# Power_Regulation.net
KiCad netlist of a schematic drawn in Altium Designer
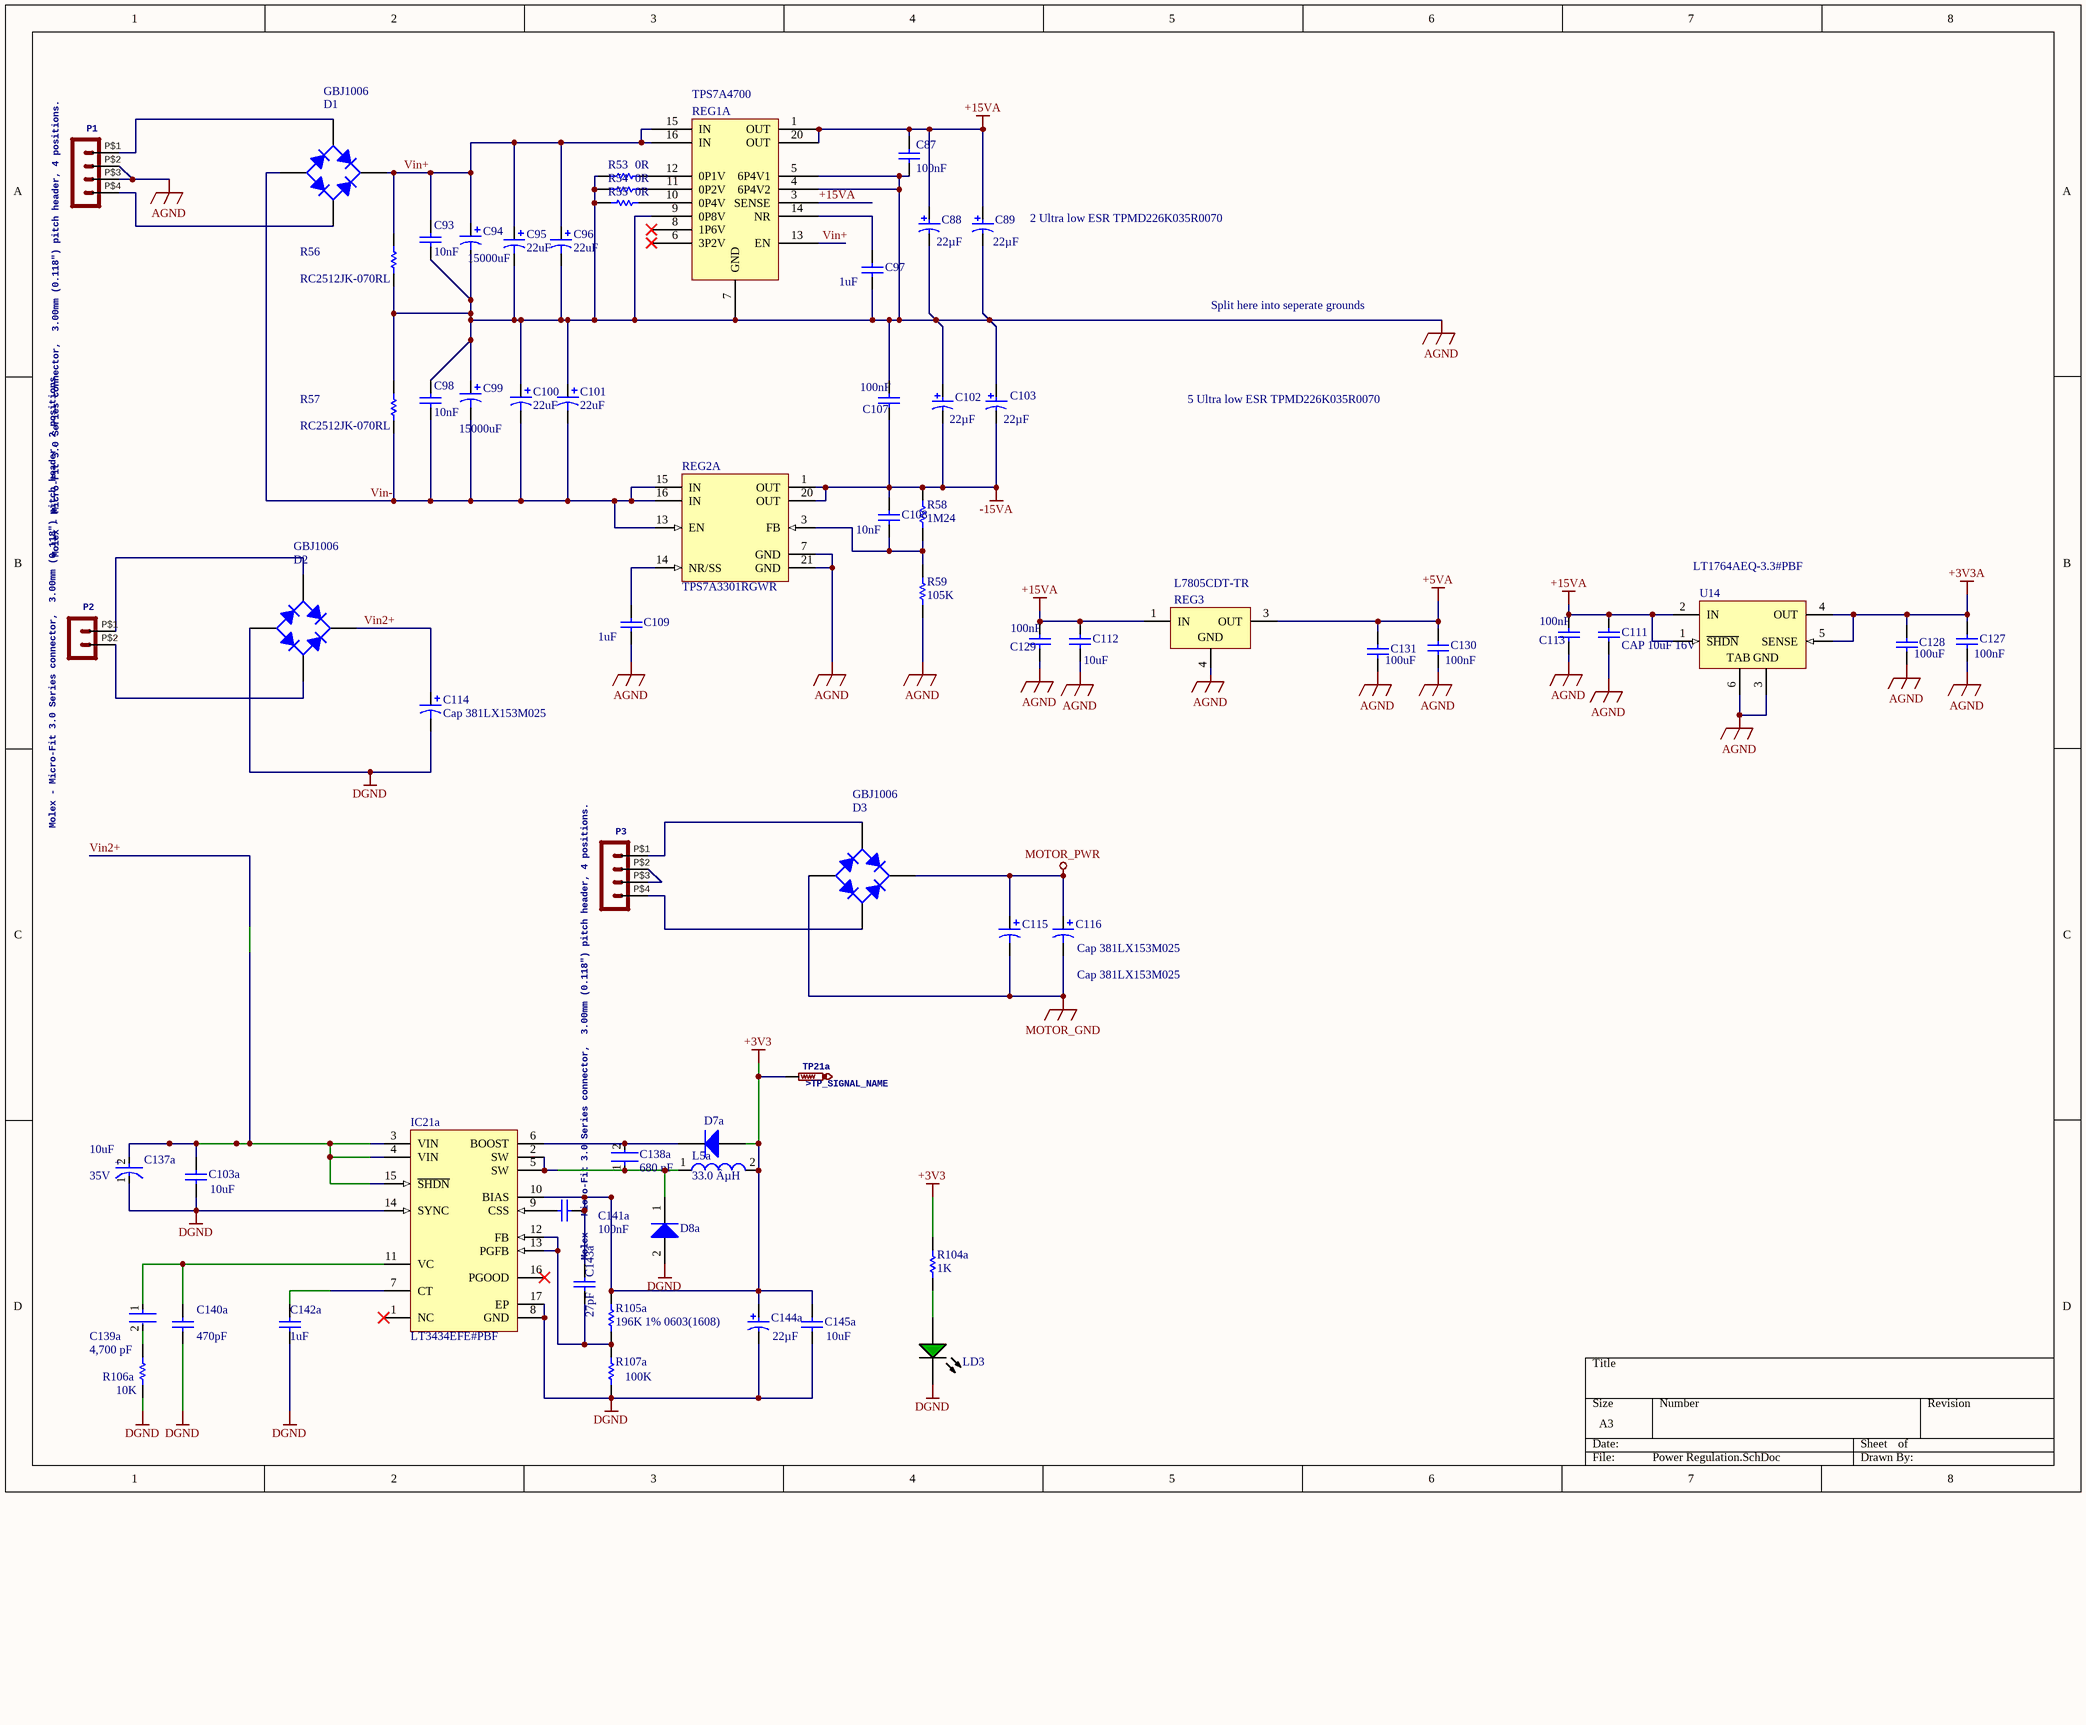
[diagram p0: Power Regulation.SchDoc]

(export (version "E")
  (design (tool "Eeschema 10.0.6"))
  (components
    (comp (ref "C87")
      (value "100nF")
      (footprint "CAPC1206(3216)190_N")
      (description "CAP 100nF 25V ±2% 1206 (3216 Metric) Thickness 1.9mm SMD")
      (fields (field (name "TOLERANCE") "Â±2%") (field (name "Comment") "CAP 100nF 25V 1206(3216)"))
      (libsource (lib "Altium Content Vault") (part "CMP-1037-04187-1"))
    )
    (comp (ref "C88")
      (value "TPSC226K025R0275")
      (footprint "CAPMP6032X28-T_V")
      (description "Low ESR, 22 uF, 25 V, +/- 10%, -55 to 125 degC, 2-Pin SMD, RoHS, Tape and Reel")
      (fields
        (field (name "TOLERANCE") "±10%")
        (field (name "CAPACITANCE") "22µF")
        (field (name "MANUFACTURER") "AVX")
      )
      (libsource (lib "Altium Content Vault") (part "CMP-2000-07295-1"))
    )
    (comp (ref "C89")
      (value "TPSC226K025R0275")
      (footprint "CAPMP6032X28-T_V")
      (description "Low ESR, 22 uF, 25 V, +/- 10%, -55 to 125 degC, 2-Pin SMD, RoHS, Tape and Reel")
      (fields
        (field (name "TOLERANCE") "±10%")
        (field (name "CAPACITANCE") "22µF")
        (field (name "MANUFACTURER") "AVX")
      )
      (libsource (lib "Altium Content Vault") (part "CMP-2000-07295-1"))
    )
    (comp (ref "C93")
      (value "10nF")
      (footprint "C0805")
      (description "Capacitor")
      (fields (field (name "Comment") "l") (field (name "PUBLISHER") "Altium Limited"))
      (libsource (lib "Miscellaneous Devices") (part "Cap"))
    )
    (comp (ref "C94")
      (value "15000uF")
      (footprint "Cap 15000uF")
      (fields (field (name "Comment") "Cap 381LX153M025"))
      (libsource (lib "CurrentSource") (part "Cap 381LX153M025"))
    )
    (comp (ref "C95")
      (value "22uF")
      (footprint "Case D")
      (libsource (lib "CurrentSource") (part "Polar Capacitor"))
    )
    (comp (ref "C96")
      (value "22uF")
      (footprint "Case D")
      (libsource (lib "CurrentSource") (part "Polar Capacitor"))
    )
    (comp (ref "C97")
      (value "1uF")
      (footprint "C1206")
      (description "Capacitor")
      (fields (field (name "Comment") "l") (field (name "PUBLISHER") "Altium Limited"))
      (libsource (lib "Miscellaneous Devices") (part "Cap"))
    )
    (comp (ref "C98")
      (value "10nF")
      (footprint "C0805")
      (description "Capacitor")
      (fields (field (name "Comment") "l") (field (name "PUBLISHER") "Altium Limited"))
      (libsource (lib "Miscellaneous Devices") (part "Cap"))
    )
    (comp (ref "C99")
      (value "15000uF")
      (footprint "Cap 15000uF")
      (fields (field (name "Comment") "Cap 381LX153M025"))
      (libsource (lib "CurrentSource") (part "Cap 381LX153M025"))
    )
    (comp (ref "C100")
      (value "22uF")
      (footprint "Case D")
      (libsource (lib "CurrentSource") (part "Polar Capacitor"))
    )
    (comp (ref "C101")
      (value "22uF")
      (footprint "Case D")
      (libsource (lib "CurrentSource") (part "Polar Capacitor"))
    )
    (comp (ref "C102")
      (value "TPSC226K025R0275")
      (footprint "CAPMP6032X28-T_V")
      (description "Low ESR, 22 uF, 25 V, +/- 10%, -55 to 125 degC, 2-Pin SMD, RoHS, Tape and Reel")
      (fields
        (field (name "TOLERANCE") "±10%")
        (field (name "CAPACITANCE") "22µF")
        (field (name "MANUFACTURER") "AVX")
      )
      (libsource (lib "Altium Content Vault") (part "CMP-2000-07295-1"))
    )
    (comp (ref "C103")
      (value "TPSC226K025R0275")
      (footprint "CAPMP6032X28-T_V")
      (description "Low ESR, 22 uF, 25 V, +/- 10%, -55 to 125 degC, 2-Pin SMD, RoHS, Tape and Reel")
      (fields
        (field (name "TOLERANCE") "±10%")
        (field (name "CAPACITANCE") "22µF")
        (field (name "MANUFACTURER") "AVX")
      )
      (libsource (lib "Altium Content Vault") (part "CMP-2000-07295-1"))
    )
    (comp (ref "C103a")
      (value "CGA6P3X7S1H106K250AB")
      (footprint "CAPC3225X280X20LL40")
      (description "Chip Capacitor, 10 uF, +/- 10%, 50 V, -55 to 125 degC, 1210 (3225 Metric), RoHS, Tape and Reel")
      (fields
        (field (name "VOLTAGE") "50V")
        (field (name "CAPACITANCE") "10uF")
        (field (name "MANUFACTURER") "TDK")
      )
      (libsource (lib "Altium Content Vault") (part "CMP-2000-07444-1"))
    )
    (comp (ref "C107")
      (value "100nF")
      (footprint "CAPC1206(3216)190_N")
      (description "CAP 100nF 25V ±2% 1206 (3216 Metric) Thickness 1.9mm SMD")
      (fields (field (name "TOLERANCE") "Â±2%") (field (name "Comment") "CAP 100nF 25V 1206(3216)"))
      (libsource (lib "Altium Content Vault") (part "CMP-1037-04187-1"))
    )
    (comp (ref "C108")
      (value "10nF")
      (footprint "C0805")
      (description "Capacitor")
      (fields (field (name "Comment") "l") (field (name "PUBLISHER") "Altium Limited"))
      (libsource (lib "Miscellaneous Devices") (part "Cap"))
    )
    (comp (ref "C109")
      (value "1uF")
      (footprint "C1206")
      (description "Capacitor")
      (fields (field (name "Comment") "l") (field (name "PUBLISHER") "Altium Limited"))
      (libsource (lib "Miscellaneous Devices") (part "Cap"))
    )
    (comp (ref "C111")
      (value "CAP 10uF 16V 1210(3225)")
      (footprint "CAPC1210(3225)230_N")
      (description "CAP 10uF 16V ±20% 1210 (3225 Metric) Thickness 2.3mm SMD")
      (fields (field (name "TOLERANCE") "Â±20%"))
      (libsource (lib "Altium Content Vault") (part "CAP"))
    )
    (comp (ref "C112")
      (value "10uF")
      (footprint "CAPC1210(3225)230_N")
      (description "CAP 10uF 16V ±20% 1210 (3225 Metric) Thickness 2.3mm SMD")
      (fields (field (name "TOLERANCE") "Â±20%") (field (name "Comment") "CAP 10uF 16V 1210(3225)"))
      (libsource (lib "Altium Content Vault") (part "CMP-1038-02218-1"))
    )
    (comp (ref "C113")
      (value "100nF")
      (footprint "CAPC1206(3216)190_N")
      (description "CAP 100nF 25V ±2% 1206 (3216 Metric) Thickness 1.9mm SMD")
      (fields (field (name "TOLERANCE") "Â±2%") (field (name "Comment") "CAP 100nF 25V 1206(3216)"))
      (libsource (lib "Altium Content Vault") (part "CMP-1037-04187-1"))
    )
    (comp (ref "C114")
      (value "Cap 381LX153M025")
      (footprint "Cap 15000uF")
      (libsource (lib "CurrentSource") (part "Cap 381LX153M025"))
    )
    (comp (ref "C115")
      (value "Cap 381LX153M025")
      (footprint "Cap 15000uF")
      (libsource (lib "CurrentSource") (part "Cap 381LX153M025"))
    )
    (comp (ref "C116")
      (value "Cap 381LX153M025")
      (footprint "Cap 15000uF")
      (libsource (lib "CurrentSource") (part "Cap 381LX153M025"))
    )
    (comp (ref "C127")
      (value "100nF")
      (footprint "CAPC1206(3216)190_N")
      (description "CAP 100nF 25V ±2% 1206 (3216 Metric) Thickness 1.9mm SMD")
      (fields (field (name "TOLERANCE") "Â±2%") (field (name "Comment") "CAP 100nF 25V 1206(3216)"))
      (libsource (lib "Altium Content Vault") (part "CMP-1037-04187-1"))
    )
    (comp (ref "C128")
      (value "100uF")
      (footprint "CAPC1210(3225)280_M")
      (description "CAP 100uF 6.3V ±20% 1210 (3225 Metric) Thickness 2.8mm SMD")
      (fields (field (name "TOLERANCE") "Â±20%") (field (name "Comment") "CAP 100uF 6.3V 1210(3225)"))
      (libsource (lib "Altium Content Vault") (part "CMP-1038-02302-1"))
    )
    (comp (ref "C129")
      (value "100nF")
      (footprint "CAPC1206(3216)190_N")
      (description "CAP 100nF 25V ±2% 1206 (3216 Metric) Thickness 1.9mm SMD")
      (fields (field (name "TOLERANCE") "Â±2%") (field (name "Comment") "CAP 100nF 25V 1206(3216)"))
      (libsource (lib "Altium Content Vault") (part "CMP-1037-04187-1"))
    )
    (comp (ref "C130")
      (value "100nF")
      (footprint "CAPC1206(3216)190_N")
      (description "CAP 100nF 25V ±2% 1206 (3216 Metric) Thickness 1.9mm SMD")
      (fields (field (name "TOLERANCE") "Â±2%") (field (name "Comment") "CAP 100nF 25V 1206(3216)"))
      (libsource (lib "Altium Content Vault") (part "CMP-1037-04187-1"))
    )
    (comp (ref "C131")
      (value "100uF")
      (footprint "CAPC1210(3225)280_M")
      (description "CAP 100uF 6.3V ±20% 1210 (3225 Metric) Thickness 2.8mm SMD")
      (fields (field (name "TOLERANCE") "Â±20%") (field (name "Comment") "CAP 100uF 6.3V 1210(3225)"))
      (libsource (lib "Altium Content Vault") (part "CMP-1038-02302-1"))
    )
    (comp (ref "C137a")
      (value "10uF")
      (footprint "FP-TAJD-MFG")
      (description "CAP TANT 10UF 20% 35V 2917")
      (fields
        (field (name "OCTOPART") "https://octopart.com/tajd106m035rnj-avx-3819655")
        (field (name "VOLTAGE RATING") "35V")
        (field (name "MANUFACTURER") "AVX")
      )
      (libsource (lib "Altium Content Vault") (part "CMP-04424-000020-1"))
    )
    (comp (ref "C138a")
      (value "680 nF")
      (footprint "FP-CC0603-DA-MFG")
      (description "CAP CER 0.68UF 16V X7R 0603")
      (fields (field (name "TOLERANCE") "0.1") (field (name "MANUFACTURER") "YAGEO"))
      (libsource (lib "Altium Content Vault") (part "CMP-03422-000082-1"))
    )
    (comp (ref "C139a")
      (value "4,700 pF")
      (footprint "FP-C0603C-CF-MFG")
      (description "CAP CER 4700PF 50V NP0 0603")
      (fields
        (field (name "TOLERANCE") "0.02")
        (field (name "OCTOPART") "https://octopart.com/c0603c472g5gactu-kemet-19050074")
      )
      (libsource (lib "Altium Content Vault") (part "CMP-03020-006967-1"))
    )
    (comp (ref "C140a")
      (value "470pF")
      (footprint "CAPC0603(1608)100_M")
      (description "CAP 470pF 50V ±5% 0603 (1608 Metric) Thickness 1mm SMD")
      (fields (field (name "TOLERANCE") "Â±5%") (field (name "Comment") "CAP 470pF 50V 0603(1608)"))
      (libsource (lib "Altium Content Vault") (part "CMP-1035-01675-1"))
    )
    (comp (ref "C141a")
      (value "100nF")
      (footprint "CAPC0805(2012)100_L")
      (description "CAP 100nF 16V ±5% 0805 (2012 Metric) Thickness 1mm SMD")
      (fields (field (name "TOLERANCE") "Â±5%") (field (name "Comment") "CAP 100nF 16V 0805(2012)"))
      (libsource (lib "Altium Content Vault") (part "CMP-1036-04400-1"))
    )
    (comp (ref "C142a")
      (value "1uF")
      (footprint "CAPC0805(2012)145_N")
      (description "CAP 1uF 6.3V ±10% 0805 (2012 Metric) Thickness 1.45mm SMD")
      (fields (field (name "TOLERANCE") "Â±10%") (field (name "Comment") "CAP 1uF 6.3V 0805(2012)"))
      (libsource (lib "Altium Content Vault") (part "CMP-1036-04731-1"))
    )
    (comp (ref "C143a")
      (value "27pF")
      (footprint "CAPC0603(1608)100_L")
      (description "CAP 27pF 50V ±10% 0603 (1608 Metric) Thickness 1mm SMD")
      (fields (field (name "TOLERANCE") "Â±10%") (field (name "Comment") "CAP 27pF 50V 0603(1608)"))
      (libsource (lib "Altium Content Vault") (part "CMP-1035-00889-1"))
    )
    (comp (ref "C144a")
      (value "TPSC226K025R0275")
      (footprint "CAPMP6032X28-T_V")
      (description "Low ESR, 22 uF, 25 V, +/- 10%, -55 to 125 degC, 2-Pin SMD, RoHS, Tape and Reel")
      (fields
        (field (name "TOLERANCE") "±10%")
        (field (name "CAPACITANCE") "22µF")
        (field (name "MANUFACTURER") "AVX")
      )
      (libsource (lib "Altium Content Vault") (part "CMP-2000-07295-1"))
    )
    (comp (ref "C145a")
      (value "CGA6P3X7S1H106K250AB")
      (footprint "CAPC3225X280X20LL40")
      (description "Chip Capacitor, 10 uF, +/- 10%, 50 V, -55 to 125 degC, 1210 (3225 Metric), RoHS, Tape and Reel")
      (fields
        (field (name "VOLTAGE") "50V")
        (field (name "CAPACITANCE") "10uF")
        (field (name "MANUFACTURER") "TDK")
      )
      (libsource (lib "Altium Content Vault") (part "CMP-2000-07444-1"))
    )
    (comp (ref "D1")
      (value "GBJ1006")
      (footprint "DIOD-GBJ-4_V")
      (description "Glass Passivated Bridge Rectifier, 10 A, -65 to 150 degC, 4-Pin THD (GBJ), Tube")
      (fields (field (name "MANUFACTURER") "Diodes Inc"))
      (libsource (lib "Altium Content Vault") (part "DIOD-GBJ1006-4"))
    )
    (comp (ref "D2")
      (value "GBJ1006")
      (footprint "DIOD-GBJ-4_V")
      (description "Glass Passivated Bridge Rectifier, 10 A, -65 to 150 degC, 4-Pin THD (GBJ), Tube")
      (fields (field (name "MANUFACTURER") "Diodes Inc"))
      (libsource (lib "Altium Content Vault") (part "CMP-1229-00001-1"))
    )
    (comp (ref "D3")
      (value "GBJ1006")
      (footprint "DIOD-GBJ-4_V")
      (description "Glass Passivated Bridge Rectifier, 10 A, -65 to 150 degC, 4-Pin THD (GBJ), Tube")
      (fields (field (name "MANUFACTURER") "Diodes Inc"))
      (libsource (lib "Altium Content Vault") (part "DIOD-GBJ1006-4"))
    )
    (comp (ref "D7a")
      (value "JANTX1N4148-1")
      (footprint "MCSM-DO-35-2")
      (description "Glass Axial Switching Diode, 200 mA, 100 V, 2-Pin DO-35, RoHS, Bulk")
      (fields (field (name "PARTNUMBER") "1N4148-1") (field (name "MANUFACTURER") "Microsemi"))
      (libsource (lib "Altium Content Vault") (part "CMP-2000-06494-1"))
    )
    (comp (ref "D8a")
      (value "MBRS3201T3G")
      (footprint "ONSC-SMC-2-403-03_V")
      (description "200 V, 3 A Schottky Fast Soft-Recovery Power Rectifier, 2-Pin SMC, Pb-Free, Tape and Reel")
      (fields (field (name "MANUFACTURER") "On Semiconductor"))
      (libsource (lib "Altium Content Vault") (part "CMP-1055-00379-1"))
    )
    (comp (ref "IC21a")
      (value "LT3434EFE#PBF")
      (footprint "LT-FE-16-EPV-BC_M")
      (fields (field (name "MANUFACTURER") "Linear Technology"))
      (libsource (lib "Altium Content Vault") (part "LT-LT3435_LT3434-FE-16"))
    )
    (comp (ref "L5a")
      (value "7447715330")
      (footprint "WE-PD-LS")
      (description "SMD-Shielded Power Inductor WE-PD, L = 33.0 µH")
      (fields (field (name "INDUCTANCE") "33.0 ÂµH"))
      (libsource (lib "Altium Content Vault") (part "CMP-0227-00710-1"))
    )
    (comp (ref "LD3")
      (value "SML-LXT0805GW-TR")
      (footprint "LUMX-SML-LXT0805_V")
      (description "LED, GREEN, 565 nm, 2 V, -25 to 80 degC, 2-Pin SMD, RoHS, Tape and Reel")
      (libsource (lib "Altium Content Vault") (part "CMP-1724-00001-1"))
    )
    (comp (ref "P1")
      (value "Molex - Micro-Fit 3.0 Series connector,  3.00mm (0.118\") pitch header, 4 positions.")
      (footprint "43650-0415")
      (libsource (lib "con-molex-micro-fit-3_0") (part "HEADER_POS4_?43650-0415"))
    )
    (comp (ref "P2")
      (value "Molex - Micro-Fit 3.0 Series connector,  3.00mm (0.118\") pitch header, 2 positions.")
      (footprint "43650-0215")
      (libsource (lib "con-molex-micro-fit-3_0") (part "HEADER_POS2_?43650-0215"))
    )
    (comp (ref "P3")
      (value "Molex - Micro-Fit 3.0 Series connector,  3.00mm (0.118\") pitch header, 4 positions.")
      (footprint "43650-0415")
      (libsource (lib "con-molex-micro-fit-3_0") (part "HEADER_POS4_?43650-0415"))
    )
    (comp (ref "R53")
      (value "RC1608J000CS")
      (footprint "RESC1608X55X35LL10T10")
      (description "Chip Resistor, 0 Ohm, +/- 5%, 0.1 W, -55 to 155 degC, 0603 (1608 Metric), RoHS, Tape and Reel")
      (fields
        (field (name "RESISTANCE (OHMS)") "0R")
        (field (name "MANUFACTURER") "Samsung-Electro-Mechanics-America,-Inc.")
        (field (name "TOLERANCE") "Jumper")
      )
      (libsource (lib "Altium Content Vault") (part "CMP-2000-06972-1"))
    )
    (comp (ref "R54")
      (value "RC1608J000CS")
      (footprint "RESC1608X55X35LL10T10")
      (description "Chip Resistor, 0 Ohm, +/- 5%, 0.1 W, -55 to 155 degC, 0603 (1608 Metric), RoHS, Tape and Reel")
      (fields
        (field (name "RESISTANCE (OHMS)") "0R")
        (field (name "MANUFACTURER") "Samsung-Electro-Mechanics-America,-Inc.")
        (field (name "TOLERANCE") "Jumper")
      )
      (libsource (lib "Altium Content Vault") (part "CMP-2000-06972-1"))
    )
    (comp (ref "R55")
      (value "RC1608J000CS")
      (footprint "RESC1608X55X35LL10T10")
      (description "Chip Resistor, 0 Ohm, +/- 5%, 0.1 W, -55 to 155 degC, 0603 (1608 Metric), RoHS, Tape and Reel")
      (fields
        (field (name "RESISTANCE (OHMS)") "0R")
        (field (name "MANUFACTURER") "Samsung-Electro-Mechanics-America,-Inc.")
        (field (name "TOLERANCE") "Jumper")
      )
      (libsource (lib "Altium Content Vault") (part "CMP-2000-06972-1"))
    )
    (comp (ref "R56")
      (value "RC2512JK-070RL")
      (footprint "RESC6431X65X50LL10T20")
      (description "Chip Resistor, 0 Ohm, Jumper, 1 W, -55 to 125 degC, 2512 (6432 Metric)， RoHS, Tape and Reel")
      (fields (field (name "MANUFACTURER") "Yageo"))
      (libsource (lib "Altium Content Vault") (part "RES-2"))
    )
    (comp (ref "R57")
      (value "RC2512JK-070RL")
      (footprint "RESC6431X65X50LL10T20")
      (description "Chip Resistor, 0 Ohm, Jumper, 1 W, -55 to 125 degC, 2512 (6432 Metric)， RoHS, Tape and Reel")
      (fields (field (name "MANUFACTURER") "Yageo"))
      (libsource (lib "Altium Content Vault") (part "RES-2"))
    )
    (comp (ref "R58")
      (value "1M24")
      (footprint "RESC0805(2012)_N")
      (description "1M 0.125W 1% 0805 (2012 Metric)  SMD")
      (fields (field (name "POWER") "0.125 W") (field (name "TOLERANCE") "1 %"))
      (libsource (lib "Altium Content Vault") (part "CMP-1013-00849-1"))
    )
    (comp (ref "R59")
      (value "105K")
      (footprint "RESC0805(2012)_N")
      (description "1M 0.125W 1% 0805 (2012 Metric)  SMD")
      (fields (field (name "POWER") "0.125 W") (field (name "TOLERANCE") "1 %"))
      (libsource (lib "Altium Content Vault") (part "CMP-1013-00849-1"))
    )
    (comp (ref "R104a")
      (value "1K")
      (footprint "RESC0805(2012)_M")
      (description "1K 0.125W 1% 0805 (2012 Metric)  SMD")
      (fields (field (name "TOLERANCE") "1 %") (field (name "POWER") "0.125 W"))
      (libsource (lib "Altium Content Vault") (part "CMP-1013-00510-1"))
    )
    (comp (ref "R105a")
      (value "196K 1% 0603(1608)")
      (footprint "RESC0603(1608)_L")
      (description "196K 0.1W 1% 0603 (1608 Metric)  SMD")
      (fields (field (name "POWER") "0.1 W") (field (name "TOLERANCE") "1 %"))
      (libsource (lib "Altium Content Vault") (part "RES"))
    )
    (comp (ref "R106a")
      (value "10K")
      (footprint "RESC0805(2012)_L")
      (description "10K 0.125W 5% 0805 (2012 Metric)  SMD")
      (fields (field (name "TOLERANCE") "5 %") (field (name "POWER") "0.125 W"))
      (libsource (lib "Altium Content Vault") (part "CMP-1013-00098-1"))
    )
    (comp (ref "R107a")
      (value "RC0603FR-07100KL")
      (footprint "RESC1608X55X25ML10T15")
      (description "Chip Resistor, 100 KOhm, +/- 1%, 0.1 W, -55 to 155 degC, 0603 (1608 Metric), RoHS, Tape and Reel")
      (fields
        (field (name "RESISTANCE") "100K")
        (field (name "MANUFACTURER") "Yageo")
        (field (name "TOLERANCE") "1%")
      )
      (libsource (lib "Altium Content Vault") (part "CMP-2100-03662-1"))
    )
    (comp (ref "REG1")
      (value "TPS7A4700")
      (footprint "RGW0020A_V")
      (libsource (lib "CurrentSource") (part "TPS7A4700"))
    )
    (comp (ref "REG2")
      (value "TPS7A3301RGWR")
      (footprint "RGW0020A_V")
      (fields (field (name "MANUFACTURER") "Texas Instruments"))
      (libsource (lib "Altium Content Vault") (part "CMP-0395-01391-2"))
    )
    (comp (ref "REG3")
      (value "L7805CDT-TR")
      (footprint "TO-252_N")
      (description "Positive Voltage Regulator, 3-Pin DPAK, Tape and Reel")
      (libsource (lib "Altium Content Vault") (part "PM-REG-L4940-SOT3"))
    )
    (comp (ref "TP21a")
      (value "PTR1PAD1-13")
      (footprint "P1-13")
      (description "TEST PIN")
      (fields (field (name "TP_SIGNAL_NAME") ">TP_SIGNAL_NAME"))
      (libsource (lib "testpad") (part "PTR1PAD1-13"))
    )
    (comp (ref "U14")
      (value "LT1764AEQ-3.3#PBF")
      (footprint "LT-Q-5_L")
      (fields (field (name "MANUFACTURER") "Linear Technology"))
      (libsource (lib "Altium Content Vault") (part "LT-LT1764A-Q-5"))
    )
  )
  (nets
    (net (code "1") (name "+3V3") (class "Default")
      (node (ref "C141a") (pin "2") (pinfunction "2_2") (pintype "passive"))
      (node (ref "C143a") (pin "2") (pinfunction "2_2") (pintype "passive"))
      (node (ref "C144a") (pin "1") (pinfunction "1_1") (pintype "passive"))
      (node (ref "C145a") (pin "2") (pinfunction "2_2") (pintype "passive"))
      (node (ref "D7a") (pin "1") (pinfunction "A_1") (pintype "passive"))
      (node (ref "IC21a") (pin "10") (pinfunction "BIAS_10") (pintype "power_in"))
      (node (ref "L5a") (pin "2") (pinfunction "2_2") (pintype "passive"))
      (node (ref "R104a") (pin "2") (pinfunction "2_2") (pintype "passive"))
      (node (ref "R105a") (pin "1") (pinfunction "1_1") (pintype "passive"))
      (node (ref "TP21a") (pin "TP") (pinfunction "TP_TP") (pintype "passive"))
    )
    (net (code "2") (name "+3V3A") (class "Default")
      (node (ref "C127") (pin "2") (pinfunction "2_2") (pintype "passive"))
      (node (ref "C128") (pin "1") (pinfunction "1_1") (pintype "passive"))
      (node (ref "U14") (pin "4") (pinfunction "OUT_4") (pintype "power_in"))
      (node (ref "U14") (pin "5") (pinfunction "SENSE_5") (pintype "input"))
    )
    (net (code "3") (name "+5VA") (class "Default")
      (node (ref "C130") (pin "2") (pinfunction "2_2") (pintype "passive"))
      (node (ref "C131") (pin "1") (pinfunction "1_1") (pintype "passive"))
      (node (ref "REG3") (pin "3") (pinfunction "OUT_3") (pintype "power_in"))
    )
    (net (code "4") (name "+15VA") (class "Default")
      (node (ref "C111") (pin "1") (pinfunction "1_1") (pintype "passive"))
      (node (ref "C112") (pin "1") (pinfunction "1_1") (pintype "passive"))
      (node (ref "C113") (pin "2") (pinfunction "2_2") (pintype "passive"))
      (node (ref "C129") (pin "2") (pinfunction "2_2") (pintype "passive"))
      (node (ref "C87") (pin "2") (pinfunction "2_2") (pintype "passive"))
      (node (ref "C88") (pin "1") (pinfunction "1_1") (pintype "passive"))
      (node (ref "C89") (pin "1") (pinfunction "1_1") (pintype "passive"))
      (node (ref "REG1") (pin "1") (pinfunction "OUT_1") (pintype "passive"))
      (node (ref "REG1") (pin "20") (pinfunction "OUT_20") (pintype "passive"))
      (node (ref "REG1") (pin "3") (pinfunction "SENSE_3") (pintype "passive"))
      (node (ref "REG3") (pin "1") (pinfunction "IN_1") (pintype "power_in"))
      (node (ref "U14") (pin "1") (pinfunction "~{SHDN}_1") (pintype "input"))
      (node (ref "U14") (pin "2") (pinfunction "IN_2") (pintype "power_in"))
    )
    (net (code "5") (name "-15VA") (class "Default")
      (node (ref "C102") (pin "2") (pinfunction "2_2") (pintype "passive"))
      (node (ref "C103") (pin "2") (pinfunction "2_2") (pintype "passive"))
      (node (ref "C107") (pin "1") (pinfunction "1_1") (pintype "passive"))
      (node (ref "C108") (pin "2") (pinfunction "2_2") (pintype "passive"))
      (node (ref "R58") (pin "2") (pinfunction "2_2") (pintype "passive"))
      (node (ref "REG2") (pin "1") (pinfunction "OUT_1") (pintype "power_in"))
      (node (ref "REG2") (pin "20") (pinfunction "OUT_20") (pintype "power_in"))
    )
    (net (code "6") (name "/Vin+") (class "Default")
      (node (ref "C93") (pin "2") (pinfunction "2_2") (pintype "passive"))
      (node (ref "C94") (pin "1") (pinfunction "1_1") (pintype "passive"))
      (node (ref "C95") (pin "1") (pinfunction "1_1") (pintype "passive"))
      (node (ref "C96") (pin "1") (pinfunction "1_1") (pintype "passive"))
      (node (ref "D1") (pin "1") (pinfunction "A_1") (pintype "passive"))
      (node (ref "R56") (pin "2") (pinfunction "2_2") (pintype "passive"))
      (node (ref "REG1") (pin "13") (pinfunction "EN_13") (pintype "passive"))
      (node (ref "REG1") (pin "15") (pinfunction "IN_15") (pintype "passive"))
      (node (ref "REG1") (pin "16") (pinfunction "IN_16") (pintype "passive"))
    )
    (net (code "7") (name "/Vin-") (class "Default")
      (node (ref "C100") (pin "2") (pinfunction "2_2") (pintype "passive"))
      (node (ref "C101") (pin "2") (pinfunction "2_2") (pintype "passive"))
      (node (ref "C98") (pin "1") (pinfunction "1_1") (pintype "passive"))
      (node (ref "C99") (pin "2") (pinfunction "2_2") (pintype "passive"))
      (node (ref "D1") (pin "4") (pinfunction "K_4") (pintype "passive"))
      (node (ref "R57") (pin "1") (pinfunction "1_1") (pintype "passive"))
      (node (ref "REG2") (pin "13") (pinfunction "EN_13") (pintype "input"))
      (node (ref "REG2") (pin "15") (pinfunction "IN_15") (pintype "power_in"))
      (node (ref "REG2") (pin "16") (pinfunction "IN_16") (pintype "power_in"))
    )
    (net (code "8") (name "/Vin2+") (class "Default")
      (node (ref "C103a") (pin "2") (pinfunction "2_2") (pintype "passive"))
      (node (ref "C114") (pin "1") (pinfunction "1_1") (pintype "passive"))
      (node (ref "C137a") (pin "2") (pinfunction "A_2") (pintype "passive"))
      (node (ref "D2") (pin "1") (pinfunction "A_1") (pintype "passive"))
      (node (ref "IC21a") (pin "15") (pinfunction "~{SHDN}_15") (pintype "input"))
      (node (ref "IC21a") (pin "3") (pinfunction "VIN_3") (pintype "power_in"))
      (node (ref "IC21a") (pin "4") (pinfunction "VIN_4") (pintype "power_in"))
    )
    (net (code "9") (name "AGND") (class "Default")
      (node (ref "C100") (pin "1") (pinfunction "1_1") (pintype "passive"))
      (node (ref "C101") (pin "1") (pinfunction "1_1") (pintype "passive"))
      (node (ref "C102") (pin "1") (pinfunction "1_1") (pintype "passive"))
      (node (ref "C103") (pin "1") (pinfunction "1_1") (pintype "passive"))
      (node (ref "C107") (pin "2") (pinfunction "2_2") (pintype "passive"))
      (node (ref "C109") (pin "1") (pinfunction "1_1") (pintype "passive"))
      (node (ref "C111") (pin "2") (pinfunction "2_2") (pintype "passive"))
      (node (ref "C112") (pin "2") (pinfunction "2_2") (pintype "passive"))
      (node (ref "C113") (pin "1") (pinfunction "1_1") (pintype "passive"))
      (node (ref "C127") (pin "1") (pinfunction "1_1") (pintype "passive"))
      (node (ref "C128") (pin "2") (pinfunction "2_2") (pintype "passive"))
      (node (ref "C129") (pin "1") (pinfunction "1_1") (pintype "passive"))
      (node (ref "C130") (pin "1") (pinfunction "1_1") (pintype "passive"))
      (node (ref "C131") (pin "2") (pinfunction "2_2") (pintype "passive"))
      (node (ref "C87") (pin "1") (pinfunction "1_1") (pintype "passive"))
      (node (ref "C88") (pin "2") (pinfunction "2_2") (pintype "passive"))
      (node (ref "C89") (pin "2") (pinfunction "2_2") (pintype "passive"))
      (node (ref "C93") (pin "1") (pinfunction "1_1") (pintype "passive"))
      (node (ref "C94") (pin "2") (pinfunction "2_2") (pintype "passive"))
      (node (ref "C95") (pin "2") (pinfunction "2_2") (pintype "passive"))
      (node (ref "C96") (pin "2") (pinfunction "2_2") (pintype "passive"))
      (node (ref "C97") (pin "1") (pinfunction "1_1") (pintype "passive"))
      (node (ref "C98") (pin "2") (pinfunction "2_2") (pintype "passive"))
      (node (ref "C99") (pin "1") (pinfunction "1_1") (pintype "passive"))
      (node (ref "P1") (pin "P$2") (pinfunction "2_P$2") (pintype "passive"))
      (node (ref "P1") (pin "P$3") (pinfunction "3_P$3") (pintype "passive"))
      (node (ref "R53") (pin "1") (pinfunction "1_1") (pintype "passive"))
      (node (ref "R54") (pin "1") (pinfunction "1_1") (pintype "passive"))
      (node (ref "R55") (pin "1") (pinfunction "1_1") (pintype "passive"))
      (node (ref "R56") (pin "1") (pinfunction "1_1") (pintype "passive"))
      (node (ref "R57") (pin "2") (pinfunction "2_2") (pintype "passive"))
      (node (ref "R59") (pin "1") (pinfunction "1_1") (pintype "passive"))
      (node (ref "REG1") (pin "4") (pinfunction "6P4V2_4") (pintype "passive"))
      (node (ref "REG1") (pin "5") (pinfunction "6P4V1_5") (pintype "passive"))
      (node (ref "REG1") (pin "7") (pinfunction "GND_7") (pintype "passive"))
      (node (ref "REG1") (pin "9") (pinfunction "0P8V_9") (pintype "passive"))
      (node (ref "REG2") (pin "21") (pinfunction "GND_21") (pintype "power_in"))
      (node (ref "REG2") (pin "7") (pinfunction "GND_7") (pintype "power_in"))
      (node (ref "REG3") (pin "4") (pinfunction "GND_4") (pintype "power_in"))
      (node (ref "U14") (pin "3") (pinfunction "GND_3") (pintype "power_in"))
      (node (ref "U14") (pin "6") (pinfunction "TAB_6") (pintype "power_in"))
    )
    (net (code "10") (name "DGND") (class "Default")
      (node (ref "C103a") (pin "1") (pinfunction "1_1") (pintype "passive"))
      (node (ref "C114") (pin "2") (pinfunction "2_2") (pintype "passive"))
      (node (ref "C137a") (pin "1") (pinfunction "C_1") (pintype "passive"))
      (node (ref "C140a") (pin "1") (pinfunction "1_1") (pintype "passive"))
      (node (ref "C142a") (pin "1") (pinfunction "1_1") (pintype "passive"))
      (node (ref "C144a") (pin "2") (pinfunction "2_2") (pintype "passive"))
      (node (ref "C145a") (pin "1") (pinfunction "1_1") (pintype "passive"))
      (node (ref "D2") (pin "4") (pinfunction "K_4") (pintype "passive"))
      (node (ref "D8a") (pin "2") (pinfunction "A_2") (pintype "passive"))
      (node (ref "IC21a") (pin "14") (pinfunction "SYNC_14") (pintype "input"))
      (node (ref "IC21a") (pin "17") (pinfunction "EP_17") (pintype "power_in"))
      (node (ref "IC21a") (pin "8") (pinfunction "GND_8") (pintype "power_in"))
      (node (ref "LD3") (pin "2") (pinfunction "K_2") (pintype "passive"))
      (node (ref "R106a") (pin "1") (pinfunction "1_1") (pintype "passive"))
      (node (ref "R107a") (pin "1") (pinfunction "1_1") (pintype "passive"))
    )
    (net (code "11") (name "MOTOR_GND") (class "Default")
      (node (ref "C115") (pin "2") (pinfunction "2_2") (pintype "passive"))
      (node (ref "C116") (pin "2") (pinfunction "2_2") (pintype "passive"))
      (node (ref "D3") (pin "4") (pinfunction "K_4") (pintype "passive"))
    )
    (net (code "12") (name "MOTOR_PWR") (class "Default")
      (node (ref "C115") (pin "1") (pinfunction "1_1") (pintype "passive"))
      (node (ref "C116") (pin "1") (pinfunction "1_1") (pintype "passive"))
      (node (ref "D3") (pin "1") (pinfunction "A_1") (pintype "passive"))
    )
    (net (code "13") (name "Net-(C139a-Pad2)") (class "Default")
      (node (ref "C139a") (pin "2") (pinfunction "2_2") (pintype "passive"))
      (node (ref "R106a") (pin "2") (pinfunction "2_2") (pintype "passive"))
    )
    (net (code "14") (name "Net-(D7a-K)") (class "Default")
      (node (ref "C138a") (pin "2") (pinfunction "2_2") (pintype "passive"))
      (node (ref "D7a") (pin "2") (pinfunction "K_2") (pintype "passive"))
      (node (ref "IC21a") (pin "6") (pinfunction "BOOST_6") (pintype "passive"))
    )
    (net (code "15") (name "Net-(D8a-K)") (class "Default")
      (node (ref "C138a") (pin "1") (pinfunction "1_1") (pintype "passive"))
      (node (ref "D8a") (pin "1") (pinfunction "K_1") (pintype "passive"))
      (node (ref "IC21a") (pin "2") (pinfunction "SW_2") (pintype "power_in"))
      (node (ref "IC21a") (pin "5") (pinfunction "SW_5") (pintype "power_in"))
      (node (ref "L5a") (pin "1") (pinfunction "1_1") (pintype "passive"))
    )
    (net (code "16") (name "Net-(IC21a-CSS)") (class "Default")
      (node (ref "C141a") (pin "1") (pinfunction "1_1") (pintype "passive"))
      (node (ref "IC21a") (pin "9") (pinfunction "CSS_9") (pintype "input"))
    )
    (net (code "17") (name "Net-(IC21a-CT)") (class "Default")
      (node (ref "C142a") (pin "2") (pinfunction "2_2") (pintype "passive"))
      (node (ref "IC21a") (pin "7") (pinfunction "CT_7") (pintype "passive"))
    )
    (net (code "18") (name "Net-(IC21a-FB)") (class "Default")
      (node (ref "C143a") (pin "1") (pinfunction "1_1") (pintype "passive"))
      (node (ref "IC21a") (pin "12") (pinfunction "FB_12") (pintype "input"))
      (node (ref "IC21a") (pin "13") (pinfunction "PGFB_13") (pintype "input"))
      (node (ref "R105a") (pin "2") (pinfunction "2_2") (pintype "passive"))
      (node (ref "R107a") (pin "2") (pinfunction "2_2") (pintype "passive"))
    )
    (net (code "19") (name "Net-(IC21a-VC)") (class "Default")
      (node (ref "C139a") (pin "1") (pinfunction "1_1") (pintype "passive"))
      (node (ref "C140a") (pin "2") (pinfunction "2_2") (pintype "passive"))
      (node (ref "IC21a") (pin "11") (pinfunction "VC_11") (pintype "passive"))
    )
    (net (code "20") (name "Net-(LD3-A)") (class "Default")
      (node (ref "LD3") (pin "1") (pinfunction "A_1") (pintype "passive"))
      (node (ref "R104a") (pin "1") (pinfunction "1_1") (pintype "passive"))
    )
    (net (code "21") (name "Net-(P1-1)") (class "Default")
      (node (ref "D1") (pin "2") (pinfunction "C_2") (pintype "passive"))
      (node (ref "P1") (pin "P$1") (pinfunction "1_P$1") (pintype "passive"))
    )
    (net (code "22") (name "Net-(P1-4)") (class "Default")
      (node (ref "D1") (pin "3") (pinfunction "C_3") (pintype "passive"))
      (node (ref "P1") (pin "P$4") (pinfunction "4_P$4") (pintype "passive"))
    )
    (net (code "23") (name "Net-(P2-1)") (class "Default")
      (node (ref "D2") (pin "2") (pinfunction "C_2") (pintype "passive"))
      (node (ref "P2") (pin "P$1") (pinfunction "1_P$1") (pintype "passive"))
    )
    (net (code "24") (name "Net-(P2-2)") (class "Default")
      (node (ref "D2") (pin "3") (pinfunction "C_3") (pintype "passive"))
      (node (ref "P2") (pin "P$2") (pinfunction "2_P$2") (pintype "passive"))
    )
    (net (code "25") (name "Net-(P3-1)") (class "Default")
      (node (ref "D3") (pin "2") (pinfunction "C_2") (pintype "passive"))
      (node (ref "P3") (pin "P$1") (pinfunction "1_P$1") (pintype "passive"))
    )
    (net (code "26") (name "Net-(P3-2)") (class "Default")
      (node (ref "P3") (pin "P$2") (pinfunction "2_P$2") (pintype "passive"))
      (node (ref "P3") (pin "P$3") (pinfunction "3_P$3") (pintype "passive"))
    )
    (net (code "27") (name "Net-(P3-4)") (class "Default")
      (node (ref "D3") (pin "3") (pinfunction "C_3") (pintype "passive"))
      (node (ref "P3") (pin "P$4") (pinfunction "4_P$4") (pintype "passive"))
    )
    (net (code "28") (name "Net-(REG1A-0P1V)") (class "Default")
      (node (ref "R53") (pin "2") (pinfunction "2_2") (pintype "passive"))
      (node (ref "REG1") (pin "12") (pinfunction "0P1V_12") (pintype "passive"))
    )
    (net (code "29") (name "Net-(REG1A-0P2V)") (class "Default")
      (node (ref "R54") (pin "2") (pinfunction "2_2") (pintype "passive"))
      (node (ref "REG1") (pin "11") (pinfunction "0P2V_11") (pintype "passive"))
    )
    (net (code "30") (name "Net-(REG1A-0P4V)") (class "Default")
      (node (ref "R55") (pin "2") (pinfunction "2_2") (pintype "passive"))
      (node (ref "REG1") (pin "10") (pinfunction "0P4V_10") (pintype "passive"))
    )
    (net (code "31") (name "Net-(REG1A-NR)") (class "Default")
      (node (ref "C97") (pin "2") (pinfunction "2_2") (pintype "passive"))
      (node (ref "REG1") (pin "14") (pinfunction "NR_14") (pintype "passive"))
    )
    (net (code "32") (name "Net-(REG2A-FB)") (class "Default")
      (node (ref "C108") (pin "1") (pinfunction "1_1") (pintype "passive"))
      (node (ref "R58") (pin "1") (pinfunction "1_1") (pintype "passive"))
      (node (ref "R59") (pin "2") (pinfunction "2_2") (pintype "passive"))
      (node (ref "REG2") (pin "3") (pinfunction "FB_3") (pintype "input"))
    )
    (net (code "33") (name "Net-(REG2A-NR{slash}SS)") (class "Default")
      (node (ref "C109") (pin "2") (pinfunction "2_2") (pintype "passive"))
      (node (ref "REG2") (pin "14") (pinfunction "NR/SS_14") (pintype "input"))
    )
    (net (code "34") (name "unconnected-(IC21a-NC-Pad1)") (class "Default")
      (node (ref "IC21a") (pin "1") (pinfunction "NC_1") (pintype "passive+no_connect"))
    )
    (net (code "35") (name "unconnected-(IC21a-PGOOD-Pad16)") (class "Default")
      (node (ref "IC21a") (pin "16") (pinfunction "PGOOD_16") (pintype "tri_state+no_connect"))
    )
    (net (code "36") (name "unconnected-(REG1A-1P6V-Pad8)") (class "Default")
      (node (ref "REG1") (pin "8") (pinfunction "1P6V_8") (pintype "passive+no_connect"))
    )
    (net (code "37") (name "unconnected-(REG1A-3P2V-Pad6)") (class "Default")
      (node (ref "REG1") (pin "6") (pinfunction "3P2V_6") (pintype "passive+no_connect"))
    )
  )
)
